# Schematic.net
KiCad netlist of a schematic drawn in Altium Designer
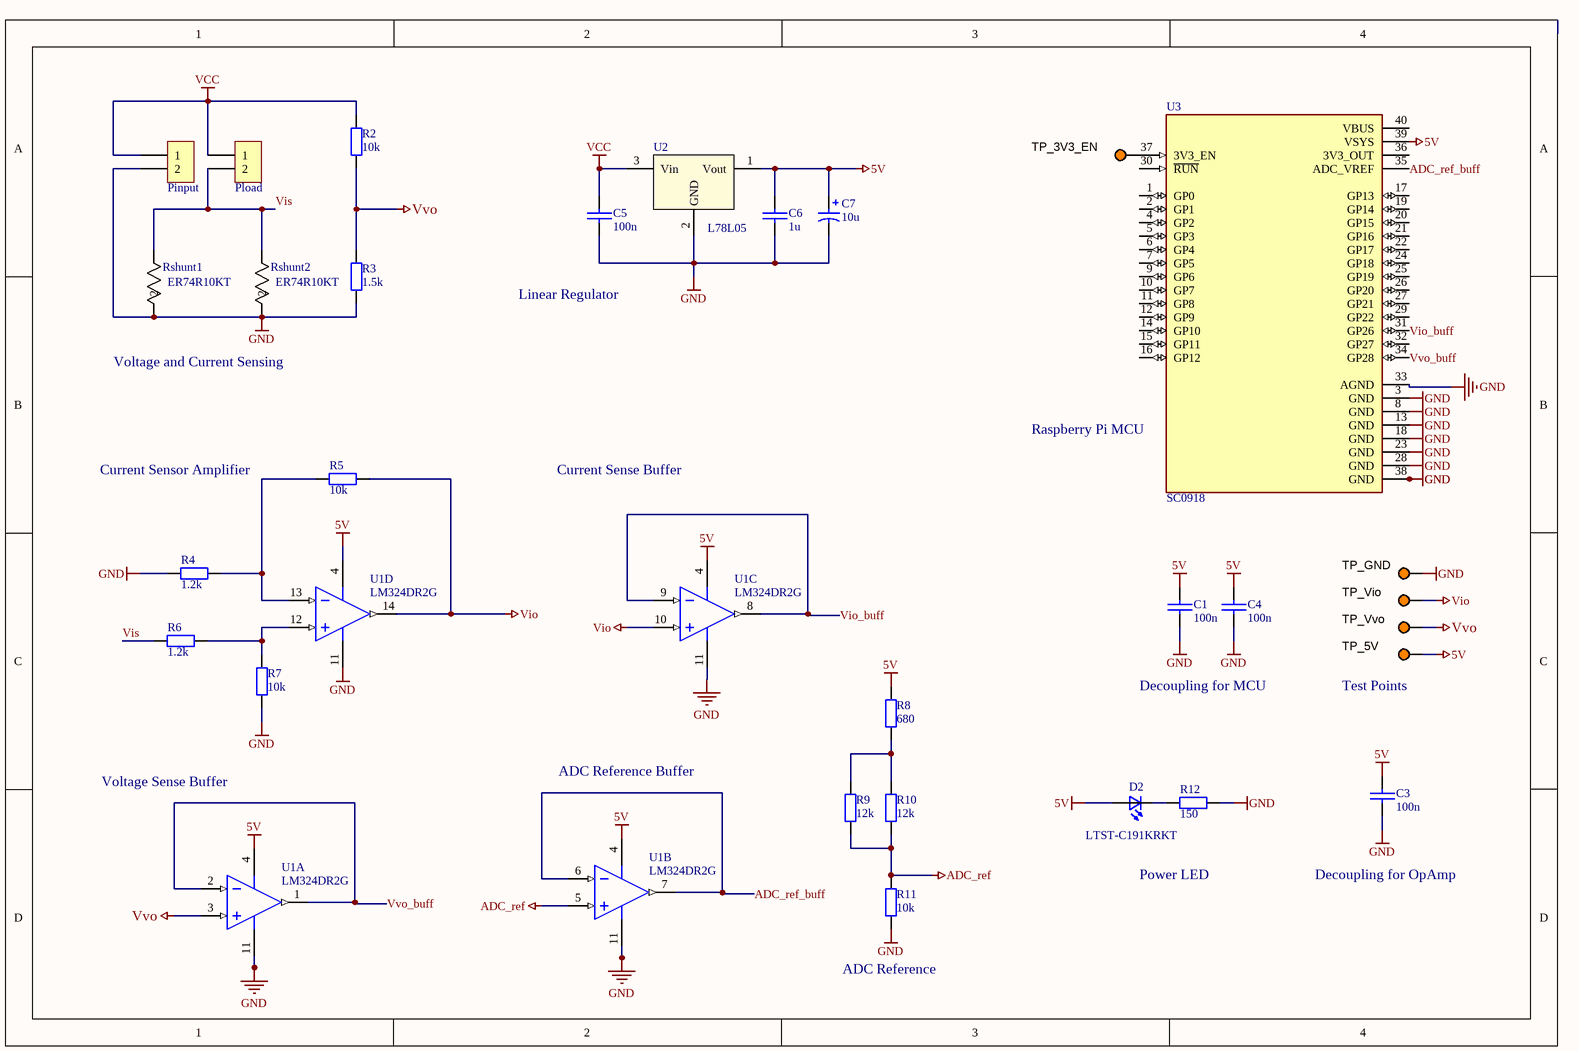
[diagram p0: Schematic.SchDoc]

(export (version "E")
  (design (tool "Eeschema 10.0.6"))
  (components
    (comp (ref "C1")
      (value "100n")
      (footprint "0805 CAP")
      (description "SMT ceramic capacitor 0805 size")
      (libsource (lib "EE209_Library") (part "CerCap_SMT_0805"))
    )
    (comp (ref "C3")
      (value "100n")
      (footprint "0805 CAP")
      (description "SMT ceramic capacitor 0805 size")
      (libsource (lib "EE209_Library") (part "CerCap_SMT_0805"))
    )
    (comp (ref "C4")
      (value "100n")
      (footprint "0805 CAP")
      (description "SMT ceramic capacitor 0805 size")
      (libsource (lib "EE209_Library") (part "CerCap_SMT_0805"))
    )
    (comp (ref "C5")
      (value "100n")
      (footprint "0805 CAP")
      (description "SMT ceramic capacitor 0805 size")
      (libsource (lib "EE209_Library") (part "CerCap_SMT_0805"))
    )
    (comp (ref "C6")
      (value "1u")
      (footprint "0805 CAP")
      (description "SMT ceramic capacitor 0805 size")
      (libsource (lib "EE209_Library") (part "CerCap_SMT_0805"))
    )
    (comp (ref "C7")
      (value "10u")
      (footprint "CAP-RAD-2.5mm Pitch")
      (description "Electrolytic capacitor with radial package, 2mm pitch and 5.2mm diameter")
      (fields (field (name "PUBLISHER") "Altium Limited"))
      (libsource (lib "EE209_Library") (part "ElecCap_TH_2P0"))
    )
    (comp (ref "D2")
      (value "LTST-C191KRKT")
      (footprint "0603")
      (description "http://octopart.com/ltst-c190krkt-lite-on-549893")
      (libsource (lib "LTST-C191KRKT") (part "LTST-C191KRKT"))
    )
    (comp (ref "Pinput")
      (value "Dual Banana Plugs")
      (footprint "Dual Banana Plug")
      (description "Dual banana plugs connection to the AC load")
      (fields (field (name "PUBLISHER") "Altium Limited"))
      (libsource (lib "EE209_Library") (part "AC_Output"))
    )
    (comp (ref "Pload")
      (value "Dual Banana Plugs")
      (footprint "Dual Banana Plug")
      (description "Dual banana plugs connection to the AC load")
      (fields (field (name "PUBLISHER") "Altium Limited"))
      (libsource (lib "EE209_Library") (part "AC_Output"))
    )
    (comp (ref "R2")
      (value "10k")
      (footprint "0805 RES")
      (description "0805 resistor")
      (fields (field (name "PUBLISHER") "Altium Limited"))
      (libsource (lib "") (part "Res_SMT_0805_1"))
    )
    (comp (ref "R3")
      (value "1.5k")
      (footprint "0805 RES")
      (description "0805 resistor")
      (fields (field (name "PUBLISHER") "Altium Limited"))
      (libsource (lib "") (part "Res_SMT_0805_1"))
    )
    (comp (ref "R4")
      (value "1.2k")
      (footprint "0805 RES")
      (description "0805 resistor")
      (fields (field (name "PUBLISHER") "Altium Limited"))
      (libsource (lib "EE209_Library") (part "Res_SMT_0805"))
    )
    (comp (ref "R5")
      (value "10k")
      (footprint "0805 RES")
      (description "0805 resistor")
      (fields (field (name "PUBLISHER") "Altium Limited"))
      (libsource (lib "EE209_Library") (part "Res_SMT_0805"))
    )
    (comp (ref "R6")
      (value "1.2k")
      (footprint "0805 RES")
      (description "0805 resistor")
      (fields (field (name "PUBLISHER") "Altium Limited"))
      (libsource (lib "EE209_Library") (part "Res_SMT_0805"))
    )
    (comp (ref "R7")
      (value "10k")
      (footprint "0805 RES")
      (description "0805 resistor")
      (fields (field (name "PUBLISHER") "Altium Limited"))
      (libsource (lib "") (part "Res_SMT_0805_1"))
    )
    (comp (ref "R8")
      (value "680")
      (footprint "0805 RES")
      (description "0805 resistor")
      (fields (field (name "PUBLISHER") "Altium Limited"))
      (libsource (lib "") (part "Res_SMT_0805_1"))
    )
    (comp (ref "R9")
      (value "12k")
      (footprint "0805 RES")
      (description "0805 resistor")
      (fields (field (name "PUBLISHER") "Altium Limited"))
      (libsource (lib "") (part "Res_SMT_0805_1"))
    )
    (comp (ref "R10")
      (value "12k")
      (footprint "0805 RES")
      (description "0805 resistor")
      (fields (field (name "PUBLISHER") "Altium Limited"))
      (libsource (lib "") (part "Res_SMT_0805_1"))
    )
    (comp (ref "R11")
      (value "10k")
      (footprint "0805 RES")
      (description "0805 resistor")
      (fields (field (name "PUBLISHER") "Altium Limited"))
      (libsource (lib "") (part "Res_SMT_0805_1"))
    )
    (comp (ref "R12")
      (value "150")
      (footprint "0805 RES")
      (description "0805 resistor")
      (fields (field (name "PUBLISHER") "Altium Limited"))
      (libsource (lib "") (part "Res_SMT_0805_2"))
    )
    (comp (ref "Rshunt1")
      (value "ER74R10KT")
      (footprint "RES_ER74_TYCO_TYC")
      (description "No Description Available")
      (libsource (lib "ER74R10KT") (part "ER74R10KT"))
    )
    (comp (ref "Rshunt2")
      (value "ER74R10KT")
      (footprint "RES_ER74_TYCO_TYC")
      (description "No Description Available")
      (libsource (lib "ER74R10KT") (part "ER74R10KT"))
    )
    (comp (ref "TP_3V3_EN")
      (value "5003")
      (footprint "TP_TH")
      (description "Test Point, Orange, 1-Pin THD, RoHS")
      (libsource (lib "EE209_Library") (part "TestPoint"))
    )
    (comp (ref "TP_5V")
      (value "5003")
      (footprint "TP_TH")
      (description "Test Point, Orange, 1-Pin THD, RoHS")
      (libsource (lib "EE209_Library") (part "TestPoint"))
    )
    (comp (ref "TP_GND")
      (value "5003")
      (footprint "TP_TH")
      (description "Test Point, Orange, 1-Pin THD, RoHS")
      (libsource (lib "EE209_Library") (part "TestPoint"))
    )
    (comp (ref "TP_Vio")
      (value "5003")
      (footprint "TP_TH")
      (description "Test Point, Orange, 1-Pin THD, RoHS")
      (libsource (lib "EE209_Library") (part "TestPoint"))
    )
    (comp (ref "TP_Vvo")
      (value "5003")
      (footprint "TP_TH")
      (description "Test Point, Orange, 1-Pin THD, RoHS")
      (libsource (lib "EE209_Library") (part "TestPoint"))
    )
    (comp (ref "U1")
      (value "LM324DR2G")
      (footprint "SOIC-14")
      (fields (field (name "MANUFACTURER") "On Semiconductor"))
      (libsource (lib "EE209_Library") (part "LM324DR_SMT_SOIC16"))
    )
    (comp (ref "U2")
      (value "L78L05")
      (footprint "SOT-89")
      (description "LDO Voltage Regulator 5V")
      (libsource (lib "EE209_Library") (part "L78L05_SMT_SOT89"))
    )
    (comp (ref "U3")
      (value "SC0918")
      (footprint "RP Pico Header V2")
      (description "RP2040 Raspberry Pi Pico - ARMÂ® CortexÂ®-M0+ MCU 32-Bit Embedded Evaluation Board")
      (fields (field (name "MF") "Raspberry Pi"))
      (libsource (lib "SC0918") (part "SC0918"))
    )
  )
  (nets
    (net (code "1") (name "/ADC_ref_buff") (class "Default")
      (node (ref "U1") (pin "6") (pinfunction "IN2-_6") (pintype "input"))
      (node (ref "U1") (pin "7") (pinfunction "OUT2_7") (pintype "output"))
      (node (ref "U3") (pin "35") (pinfunction "ADC_VREF_35") (pintype "power_in"))
    )
    (net (code "2") (name "/Vio_buff") (class "Default")
      (node (ref "U1") (pin "8") (pinfunction "OUT3_8") (pintype "output"))
      (node (ref "U1") (pin "9") (pinfunction "IN3-_9") (pintype "input"))
      (node (ref "U3") (pin "31") (pinfunction "GP26_31") (pintype "bidirectional"))
    )
    (net (code "3") (name "/Vis") (class "Default")
      (node (ref "Pload") (pin "2") (pinfunction "2_2") (pintype "passive"))
      (node (ref "R6") (pin "1") (pinfunction "1_1") (pintype "passive"))
      (node (ref "Rshunt1") (pin "1") (pinfunction "1_1") (pintype "passive"))
      (node (ref "Rshunt2") (pin "1") (pinfunction "1_1") (pintype "passive"))
    )
    (net (code "4") (name "/Vvo_buff") (class "Default")
      (node (ref "U1") (pin "1") (pinfunction "OUT1_1") (pintype "output"))
      (node (ref "U1") (pin "2") (pinfunction "IN1-_2") (pintype "input"))
      (node (ref "U3") (pin "34") (pinfunction "GP28_34") (pintype "bidirectional"))
    )
    (net (code "5") (name "5V") (class "Default")
      (node (ref "C1") (pin "1") (pinfunction "1_1") (pintype "passive"))
      (node (ref "C3") (pin "1") (pinfunction "1_1") (pintype "passive"))
      (node (ref "C4") (pin "1") (pinfunction "1_1") (pintype "passive"))
      (node (ref "C6") (pin "1") (pinfunction "1_1") (pintype "passive"))
      (node (ref "C7") (pin "1") (pinfunction "1_1") (pintype "passive"))
      (node (ref "D2") (pin "2") (pinfunction "A2_2") (pintype "passive"))
      (node (ref "R8") (pin "2") (pinfunction "2_2") (pintype "passive"))
      (node (ref "TP_5V") (pin "1") (pinfunction "1_1") (pintype "passive"))
      (node (ref "U1") (pin "4") (pinfunction "VCC_4") (pintype "power_in"))
      (node (ref "U2") (pin "1") (pinfunction "Vout_1") (pintype "passive"))
      (node (ref "U3") (pin "39") (pinfunction "VSYS_39") (pintype "power_in"))
    )
    (net (code "6") (name "ADC_ref") (class "Default")
      (node (ref "R10") (pin "1") (pinfunction "1_1") (pintype "passive"))
      (node (ref "R11") (pin "2") (pinfunction "2_2") (pintype "passive"))
      (node (ref "R9") (pin "1") (pinfunction "1_1") (pintype "passive"))
      (node (ref "U1") (pin "5") (pinfunction "IN2+_5") (pintype "input"))
    )
    (net (code "7") (name "GND") (class "Default")
      (node (ref "C1") (pin "2") (pinfunction "2_2") (pintype "passive"))
      (node (ref "C3") (pin "2") (pinfunction "2_2") (pintype "passive"))
      (node (ref "C4") (pin "2") (pinfunction "2_2") (pintype "passive"))
      (node (ref "C5") (pin "2") (pinfunction "2_2") (pintype "passive"))
      (node (ref "C6") (pin "2") (pinfunction "2_2") (pintype "passive"))
      (node (ref "C7") (pin "2") (pinfunction "2_2") (pintype "passive"))
      (node (ref "Pinput") (pin "2") (pinfunction "2_2") (pintype "passive"))
      (node (ref "R11") (pin "1") (pinfunction "1_1") (pintype "passive"))
      (node (ref "R12") (pin "1") (pinfunction "1_1") (pintype "passive"))
      (node (ref "R3") (pin "1") (pinfunction "1_1") (pintype "passive"))
      (node (ref "R4") (pin "1") (pinfunction "1_1") (pintype "passive"))
      (node (ref "R7") (pin "1") (pinfunction "1_1") (pintype "passive"))
      (node (ref "Rshunt1") (pin "2") (pinfunction "2_2") (pintype "passive"))
      (node (ref "Rshunt2") (pin "2") (pinfunction "2_2") (pintype "passive"))
      (node (ref "TP_GND") (pin "1") (pinfunction "1_1") (pintype "passive"))
      (node (ref "U1") (pin "11") (pinfunction "VEE/GND_11") (pintype "power_in"))
      (node (ref "U2") (pin "2") (pinfunction "GND_2") (pintype "passive"))
      (node (ref "U3") (pin "13") (pinfunction "GND_13") (pintype "power_in"))
      (node (ref "U3") (pin "18") (pinfunction "GND_18") (pintype "power_in"))
      (node (ref "U3") (pin "23") (pinfunction "GND_23") (pintype "power_in"))
      (node (ref "U3") (pin "28") (pinfunction "GND_28") (pintype "power_in"))
      (node (ref "U3") (pin "3") (pinfunction "GND_3") (pintype "power_in"))
      (node (ref "U3") (pin "33") (pinfunction "AGND_33") (pintype "power_in"))
      (node (ref "U3") (pin "38") (pinfunction "GND_38") (pintype "power_in"))
      (node (ref "U3") (pin "8") (pinfunction "GND_8") (pintype "power_in"))
    )
    (net (code "8") (name "Net-(D2-K2)") (class "Default")
      (node (ref "D2") (pin "1") (pinfunction "K2_1") (pintype "passive"))
      (node (ref "R12") (pin "2") (pinfunction "2_2") (pintype "passive"))
    )
    (net (code "9") (name "Net-(R10-Pad2)") (class "Default")
      (node (ref "R10") (pin "2") (pinfunction "2_2") (pintype "passive"))
      (node (ref "R8") (pin "1") (pinfunction "1_1") (pintype "passive"))
      (node (ref "R9") (pin "2") (pinfunction "2_2") (pintype "passive"))
    )
    (net (code "10") (name "Net-(U1D-IN4+)") (class "Default")
      (node (ref "R6") (pin "2") (pinfunction "2_2") (pintype "passive"))
      (node (ref "R7") (pin "2") (pinfunction "2_2") (pintype "passive"))
      (node (ref "U1") (pin "12") (pinfunction "IN4+_12") (pintype "input"))
    )
    (net (code "11") (name "Net-(U1D-IN4-)") (class "Default")
      (node (ref "R4") (pin "2") (pinfunction "2_2") (pintype "passive"))
      (node (ref "R5") (pin "1") (pinfunction "1_1") (pintype "passive"))
      (node (ref "U1") (pin "13") (pinfunction "IN4-_13") (pintype "input"))
    )
    (net (code "12") (name "Net-(U3-3V3_EN)") (class "Default")
      (node (ref "TP_3V3_EN") (pin "1") (pinfunction "1_1") (pintype "passive"))
      (node (ref "U3") (pin "37") (pinfunction "3V3_EN_37") (pintype "input"))
    )
    (net (code "13") (name "VCC") (class "Default")
      (node (ref "C5") (pin "1") (pinfunction "1_1") (pintype "passive"))
      (node (ref "Pinput") (pin "1") (pinfunction "1_1") (pintype "passive"))
      (node (ref "Pload") (pin "1") (pinfunction "1_1") (pintype "passive"))
      (node (ref "R2") (pin "2") (pinfunction "2_2") (pintype "passive"))
      (node (ref "U2") (pin "3") (pinfunction "Vin_3") (pintype "passive"))
    )
    (net (code "14") (name "Vio") (class "Default")
      (node (ref "R5") (pin "2") (pinfunction "2_2") (pintype "passive"))
      (node (ref "TP_Vio") (pin "1") (pinfunction "1_1") (pintype "passive"))
      (node (ref "U1") (pin "10") (pinfunction "IN3+_10") (pintype "input"))
      (node (ref "U1") (pin "14") (pinfunction "OUT4_14") (pintype "output"))
    )
    (net (code "15") (name "Vvo") (class "Default")
      (node (ref "R2") (pin "1") (pinfunction "1_1") (pintype "passive"))
      (node (ref "R3") (pin "2") (pinfunction "2_2") (pintype "passive"))
      (node (ref "TP_Vvo") (pin "1") (pinfunction "1_1") (pintype "passive"))
      (node (ref "U1") (pin "3") (pinfunction "IN1+_3") (pintype "input"))
    )
    (net (code "16") (name "unconnected-(U3-3V3_OUT-Pad36)") (class "Default")
      (node (ref "U3") (pin "36") (pinfunction "3V3_OUT_36") (pintype "power_in"))
    )
    (net (code "17") (name "unconnected-(U3-GP0-Pad1)") (class "Default")
      (node (ref "U3") (pin "1") (pinfunction "GP0_1") (pintype "bidirectional"))
    )
    (net (code "18") (name "unconnected-(U3-GP1-Pad2)") (class "Default")
      (node (ref "U3") (pin "2") (pinfunction "GP1_2") (pintype "bidirectional"))
    )
    (net (code "19") (name "unconnected-(U3-GP2-Pad4)") (class "Default")
      (node (ref "U3") (pin "4") (pinfunction "GP2_4") (pintype "bidirectional"))
    )
    (net (code "20") (name "unconnected-(U3-GP3-Pad5)") (class "Default")
      (node (ref "U3") (pin "5") (pinfunction "GP3_5") (pintype "bidirectional"))
    )
    (net (code "21") (name "unconnected-(U3-GP4-Pad6)") (class "Default")
      (node (ref "U3") (pin "6") (pinfunction "GP4_6") (pintype "bidirectional"))
    )
    (net (code "22") (name "unconnected-(U3-GP5-Pad7)") (class "Default")
      (node (ref "U3") (pin "7") (pinfunction "GP5_7") (pintype "bidirectional"))
    )
    (net (code "23") (name "unconnected-(U3-GP6-Pad9)") (class "Default")
      (node (ref "U3") (pin "9") (pinfunction "GP6_9") (pintype "bidirectional"))
    )
    (net (code "24") (name "unconnected-(U3-GP7-Pad10)") (class "Default")
      (node (ref "U3") (pin "10") (pinfunction "GP7_10") (pintype "bidirectional"))
    )
    (net (code "25") (name "unconnected-(U3-GP8-Pad11)") (class "Default")
      (node (ref "U3") (pin "11") (pinfunction "GP8_11") (pintype "bidirectional"))
    )
    (net (code "26") (name "unconnected-(U3-GP9-Pad12)") (class "Default")
      (node (ref "U3") (pin "12") (pinfunction "GP9_12") (pintype "bidirectional"))
    )
    (net (code "27") (name "unconnected-(U3-GP10-Pad14)") (class "Default")
      (node (ref "U3") (pin "14") (pinfunction "GP10_14") (pintype "bidirectional"))
    )
    (net (code "28") (name "unconnected-(U3-GP11-Pad15)") (class "Default")
      (node (ref "U3") (pin "15") (pinfunction "GP11_15") (pintype "bidirectional"))
    )
    (net (code "29") (name "unconnected-(U3-GP12-Pad16)") (class "Default")
      (node (ref "U3") (pin "16") (pinfunction "GP12_16") (pintype "bidirectional"))
    )
    (net (code "30") (name "unconnected-(U3-GP13-Pad17)") (class "Default")
      (node (ref "U3") (pin "17") (pinfunction "GP13_17") (pintype "bidirectional"))
    )
    (net (code "31") (name "unconnected-(U3-GP14-Pad19)") (class "Default")
      (node (ref "U3") (pin "19") (pinfunction "GP14_19") (pintype "bidirectional"))
    )
    (net (code "32") (name "unconnected-(U3-GP15-Pad20)") (class "Default")
      (node (ref "U3") (pin "20") (pinfunction "GP15_20") (pintype "bidirectional"))
    )
    (net (code "33") (name "unconnected-(U3-GP16-Pad21)") (class "Default")
      (node (ref "U3") (pin "21") (pinfunction "GP16_21") (pintype "bidirectional"))
    )
    (net (code "34") (name "unconnected-(U3-GP17-Pad22)") (class "Default")
      (node (ref "U3") (pin "22") (pinfunction "GP17_22") (pintype "bidirectional"))
    )
    (net (code "35") (name "unconnected-(U3-GP18-Pad24)") (class "Default")
      (node (ref "U3") (pin "24") (pinfunction "GP18_24") (pintype "bidirectional"))
    )
    (net (code "36") (name "unconnected-(U3-GP19-Pad25)") (class "Default")
      (node (ref "U3") (pin "25") (pinfunction "GP19_25") (pintype "bidirectional"))
    )
    (net (code "37") (name "unconnected-(U3-GP20-Pad26)") (class "Default")
      (node (ref "U3") (pin "26") (pinfunction "GP20_26") (pintype "bidirectional"))
    )
    (net (code "38") (name "unconnected-(U3-GP21-Pad27)") (class "Default")
      (node (ref "U3") (pin "27") (pinfunction "GP21_27") (pintype "bidirectional"))
    )
    (net (code "39") (name "unconnected-(U3-GP22-Pad29)") (class "Default")
      (node (ref "U3") (pin "29") (pinfunction "GP22_29") (pintype "bidirectional"))
    )
    (net (code "40") (name "unconnected-(U3-GP27-Pad32)") (class "Default")
      (node (ref "U3") (pin "32") (pinfunction "GP27_32") (pintype "bidirectional"))
    )
    (net (code "41") (name "unconnected-(U3-VBUS-Pad40)") (class "Default")
      (node (ref "U3") (pin "40") (pinfunction "VBUS_40") (pintype "power_in"))
    )
    (net (code "42") (name "unconnected-(U3-~{RUN}-Pad30)") (class "Default")
      (node (ref "U3") (pin "30") (pinfunction "~{RUN}_30") (pintype "input"))
    )
  )
)
